# OurEDA-P1K_PowerManagement.net
KiCad netlist of a schematic drawn in Altium Designer
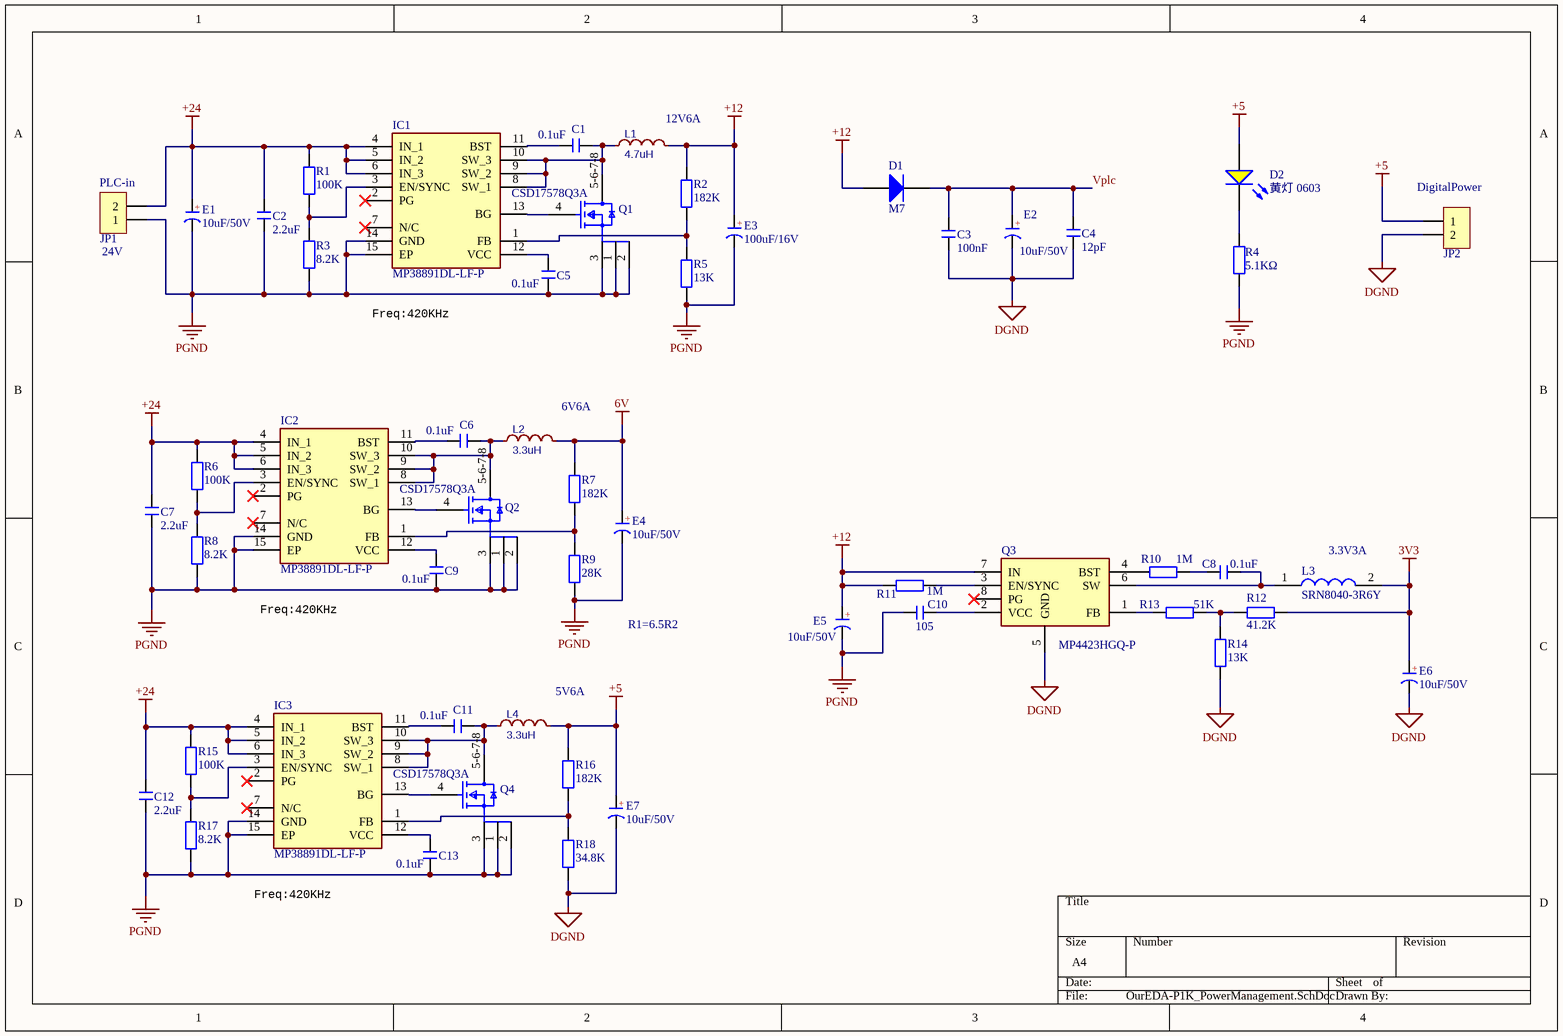
[diagram p0: OurEDA-P1K_PowerManagement.SchDoc]

(export (version "E")
  (design (tool "Eeschema 10.0.6"))
  (components
    (comp (ref "C1")
      (value "0.1uF")
      (footprint "C 0603_L")
      (description "无极性贴片电容")
      (fields (field (name "版权归属") "源创客"))
      (libsource (lib "3.1   - 电阻-电容-电感") (part "C"))
    )
    (comp (ref "C2")
      (value "2.2uF")
      (footprint "C 0805_L")
      (description "无极性贴片电容")
      (fields (field (name "版权归属") "源创客"))
      (libsource (lib "3.1   - 电阻-电容-电感") (part "C"))
    )
    (comp (ref "C3")
      (value "100nF")
      (footprint "C 0603_L")
      (description "无极性贴片电容")
      (fields (field (name "版权归属") "源创客"))
      (libsource (lib "3.1   - 电阻-电容-电感") (part "C"))
    )
    (comp (ref "C4")
      (value "12pF")
      (footprint "C 0603_L")
      (description "无极性贴片电容")
      (fields (field (name "版权归属") "源创客"))
      (libsource (lib "3.1   - 电阻-电容-电感") (part "C"))
    )
    (comp (ref "C5")
      (value "0.1uF")
      (footprint "C 0603_L")
      (description "无极性贴片电容")
      (fields (field (name "版权归属") "源创客"))
      (libsource (lib "3.1   - 电阻-电容-电感") (part "C"))
    )
    (comp (ref "C6")
      (value "0.1uF")
      (footprint "C 0603_L")
      (description "无极性贴片电容")
      (fields (field (name "版权归属") "源创客"))
      (libsource (lib "3.1   - 电阻-电容-电感") (part "C"))
    )
    (comp (ref "C7")
      (value "2.2uF")
      (footprint "C 0805_L")
      (description "无极性贴片电容")
      (fields (field (name "版权归属") "源创客"))
      (libsource (lib "3.1   - 电阻-电容-电感") (part "C"))
    )
    (comp (ref "C8")
      (value "0.1uF")
      (footprint "C 0603_L")
      (description "无极性贴片电容")
      (fields (field (name "版权归属") "源创客"))
      (libsource (lib "3.1   - 电阻-电容-电感") (part "C"))
    )
    (comp (ref "C9")
      (value "0.1uF")
      (footprint "C 0603_L")
      (description "无极性贴片电容")
      (fields (field (name "版权归属") "源创客"))
      (libsource (lib "3.1   - 电阻-电容-电感") (part "C"))
    )
    (comp (ref "C10")
      (value "105")
      (footprint "C 0603_L")
      (description "无极性贴片电容")
      (fields (field (name "版权归属") "源创客"))
      (libsource (lib "3.1   - 电阻-电容-电感") (part "C"))
    )
    (comp (ref "C11")
      (value "0.1uF")
      (footprint "C 0603_L")
      (description "无极性贴片电容")
      (fields (field (name "版权归属") "源创客"))
      (libsource (lib "3.1   - 电阻-电容-电感") (part "C"))
    )
    (comp (ref "C12")
      (value "2.2uF")
      (footprint "C 0805_L")
      (description "无极性贴片电容")
      (fields (field (name "版权归属") "源创客"))
      (libsource (lib "3.1   - 电阻-电容-电感") (part "C"))
    )
    (comp (ref "C13")
      (value "0.1uF")
      (footprint "C 0603_L")
      (description "无极性贴片电容")
      (fields (field (name "版权归属") "源创客"))
      (libsource (lib "3.1   - 电阻-电容-电感") (part "C"))
    )
    (comp (ref "D1")
      (value "M7")
      (footprint "SMA(DO-214AC)_S1")
      (description "二极管")
      (libsource (lib "Miscellaneous Devices LC") (part "SMA(DO-214AC) M7"))
    )
    (comp (ref "D2")
      (value "黄灯 0603")
      (footprint "0603_LED_S1")
      (description "发光二极管")
      (libsource (lib "Miscellaneous Devices LC") (part "0603 黄灯"))
    )
    (comp (ref "E1")
      (value "10uF/50V")
      (footprint "CM D(6.3*5.4)")
      (description "贴片电解电容")
      (fields (field (name "版权归属") "源创客"))
      (libsource (lib "3.1   - 电阻-电容-电感") (part "C-CM"))
    )
    (comp (ref "E2")
      (value "10uF/50V")
      (footprint "CM B(4*5.4)")
      (description "贴片电解电容")
      (fields (field (name "版权归属") "源创客"))
      (libsource (lib "3.1   - 电阻-电容-电感") (part "C-CM"))
    )
    (comp (ref "E3")
      (value "100uF/16V")
      (footprint "CM D(6.3*5.4)")
      (description "贴片电解电容")
      (fields (field (name "版权归属") "源创客"))
      (libsource (lib "3.1   - 电阻-电容-电感") (part "C-CM"))
    )
    (comp (ref "E4")
      (value "10uF/50V")
      (footprint "CM B(4*5.4)")
      (description "贴片电解电容")
      (fields (field (name "版权归属") "源创客"))
      (libsource (lib "3.1   - 电阻-电容-电感") (part "C-CM"))
    )
    (comp (ref "E5")
      (value "10uF/50V")
      (footprint "CM B(4*5.4)")
      (description "贴片电解电容")
      (fields (field (name "版权归属") "源创客"))
      (libsource (lib "3.1   - 电阻-电容-电感") (part "C-CM"))
    )
    (comp (ref "E6")
      (value "10uF/50V")
      (footprint "CM B(4*5.4)")
      (description "贴片电解电容")
      (fields (field (name "版权归属") "源创客"))
      (libsource (lib "3.1   - 电阻-电容-电感") (part "C-CM"))
    )
    (comp (ref "E7")
      (value "10uF/50V")
      (footprint "CM B(4*5.4)")
      (description "贴片电解电容")
      (fields (field (name "版权归属") "源创客"))
      (libsource (lib "3.1   - 电阻-电容-电感") (part "C-CM"))
    )
    (comp (ref "IC1")
      (value "MP38891DL-LF-P")
      (footprint "SON50P300X400X100-15N-D")
      (description "Integrated Circuit")
      (fields (field (name "MOUSER PART NUMBER") "946-MP38891DLLFP"))
      (libsource (lib "MySchLib") (part "MP38891DL-LF-P"))
    )
    (comp (ref "IC2")
      (value "MP38891DL-LF-P")
      (footprint "SON50P300X400X100-15N-D")
      (description "Integrated Circuit")
      (fields (field (name "MOUSER PART NUMBER") "946-MP38891DLLFP"))
      (libsource (lib "MySchLib") (part "MP38891DL-LF-P"))
    )
    (comp (ref "IC3")
      (value "MP38891DL-LF-P")
      (footprint "SON50P300X400X100-15N-D")
      (description "Integrated Circuit")
      (fields (field (name "MOUSER PART NUMBER") "946-MP38891DLLFP"))
      (libsource (lib "MySchLib") (part "MP38891DL-LF-P"))
    )
    (comp (ref "JP1")
      (value "HDR-1X2")
      (footprint "KF128-5.08-2P")
      (description "2P接插件")
      (fields (field (name "版权归属") "源创客"))
      (libsource (lib "4.10 - 接插件-脚距5.08") (part "Header 2"))
    )
    (comp (ref "JP2")
      (value "HDR-1X2")
      (footprint "HDR2.54-LI-2P")
      (description "2P接插件")
      (fields (field (name "版权归属") "源创客"))
      (libsource (lib "4.5   - 接插件-脚距2.54") (part "Header 2"))
    )
    (comp (ref "L1")
      (value "4.7uH")
      (footprint "220uH")
      (fields
        (field (name "BOM_SUPPLIER PART") "C364099")
        (field (name "BOM_MANUFACTURER PART") "SLO1235H220MTT")
        (field (name "CONTRIBUTOR") "LCSC")
      )
      (libsource (lib "MySchLib") (part "220uH"))
    )
    (comp (ref "L2")
      (value "3.3uH")
      (footprint "220uH")
      (fields
        (field (name "BOM_SUPPLIER PART") "C364099")
        (field (name "BOM_MANUFACTURER PART") "SLO1235H220MTT")
        (field (name "CONTRIBUTOR") "LCSC")
      )
      (libsource (lib "MySchLib") (part "220uH"))
    )
    (comp (ref "L3")
      (value "SRN8040-3R6Y")
      (footprint "SRN80408R2Y")
      (description "Inductor")
      (fields (field (name "MOUSER PART NUMBER") "652-SRN8040-3R6Y"))
      (libsource (lib "*") (part "SRN8040-3R6Y"))
    )
    (comp (ref "L4")
      (value "3.3uH")
      (footprint "220uH")
      (fields
        (field (name "BOM_SUPPLIER PART") "C364099")
        (field (name "BOM_MANUFACTURER PART") "SLO1235H220MTT")
        (field (name "CONTRIBUTOR") "LCSC")
      )
      (libsource (lib "MySchLib") (part "220uH"))
    )
    (comp (ref "Q1")
      (value "CSD17578Q3A")
      (footprint "FP-DNH0008A-MFG")
      (description "MOSFET N-CH 30V 35A 8VSON")
      (libsource (lib "Altium Content Vault") (part "89a476aaa9378d44880e05315291ed4"))
    )
    (comp (ref "Q2")
      (value "CSD17578Q3A")
      (footprint "FP-DNH0008A-MFG")
      (description "MOSFET N-CH 30V 35A 8VSON")
      (libsource (lib "Altium Content Vault") (part "89a476aaa9378d44880e05315291ed4"))
    )
    (comp (ref "Q3")
      (value "MP4423HGQ-P")
      (footprint "MP4423GQP")
      (description "Transistor")
      (fields (field (name "MOUSER PART NUMBER") "946-MP4423HGQ-P"))
      (libsource (lib "MySchLib") (part "MP4423HGQ-P"))
    )
    (comp (ref "Q4")
      (value "CSD17578Q3A")
      (footprint "FP-DNH0008A-MFG")
      (description "MOSFET N-CH 30V 35A 8VSON")
      (libsource (lib "Altium Content Vault") (part "89a476aaa9378d44880e05315291ed4"))
    )
    (comp (ref "R1")
      (value "100K")
      (footprint "R 0603_L")
      (description "贴片电阻")
      (fields (field (name "版权归属") "源创客"))
      (libsource (lib "3.1   - 电阻-电容-电感") (part "R"))
    )
    (comp (ref "R2")
      (value "182K")
      (footprint "R 0603_L")
      (description "贴片电阻")
      (fields (field (name "版权归属") "源创客"))
      (libsource (lib "3.1   - 电阻-电容-电感") (part "R"))
    )
    (comp (ref "R3")
      (value "8.2K")
      (footprint "R 0603_L")
      (description "贴片电阻")
      (fields (field (name "版权归属") "源创客"))
      (libsource (lib "3.1   - 电阻-电容-电感") (part "R"))
    )
    (comp (ref "R4")
      (value "5.1KΩ")
      (footprint "0603_R")
      (description "贴片电阻")
      (libsource (lib "Miscellaneous Devices LC") (part "0603 3.3KΩ (3301) 1%"))
    )
    (comp (ref "R5")
      (value "13K")
      (footprint "R 0603_L")
      (description "贴片电阻")
      (fields (field (name "版权归属") "源创客"))
      (libsource (lib "3.1   - 电阻-电容-电感") (part "R"))
    )
    (comp (ref "R6")
      (value "100K")
      (footprint "R 0603_L")
      (description "贴片电阻")
      (fields (field (name "版权归属") "源创客"))
      (libsource (lib "3.1   - 电阻-电容-电感") (part "R"))
    )
    (comp (ref "R7")
      (value "182K")
      (footprint "R 0603_L")
      (description "贴片电阻")
      (fields (field (name "版权归属") "源创客"))
      (libsource (lib "3.1   - 电阻-电容-电感") (part "R"))
    )
    (comp (ref "R8")
      (value "8.2K")
      (footprint "R 0603_L")
      (description "贴片电阻")
      (fields (field (name "版权归属") "源创客"))
      (libsource (lib "3.1   - 电阻-电容-电感") (part "R"))
    )
    (comp (ref "R9")
      (value "28K")
      (footprint "R 0603_L")
      (description "贴片电阻")
      (fields (field (name "版权归属") "源创客"))
      (libsource (lib "3.1   - 电阻-电容-电感") (part "R"))
    )
    (comp (ref "R10")
      (value "1M")
      (footprint "R 0603_L")
      (description "贴片电阻")
      (fields (field (name "版权归属") "源创客"))
      (libsource (lib "3.1   - 电阻-电容-电感") (part "R"))
    )
    (comp (ref "R11")
      (value "1M")
      (footprint "R 0603_L")
      (description "贴片电阻")
      (fields (field (name "版权归属") "源创客"))
      (libsource (lib "3.1   - 电阻-电容-电感") (part "R"))
    )
    (comp (ref "R12")
      (value "41.2K")
      (footprint "R 0603_L")
      (description "贴片电阻")
      (fields (field (name "版权归属") "源创客"))
      (libsource (lib "3.1   - 电阻-电容-电感") (part "R"))
    )
    (comp (ref "R13")
      (value "51K")
      (footprint "R 0603_L")
      (description "贴片电阻")
      (fields (field (name "版权归属") "源创客"))
      (libsource (lib "3.1   - 电阻-电容-电感") (part "R"))
    )
    (comp (ref "R14")
      (value "13K")
      (footprint "R 0603_L")
      (description "贴片电阻")
      (fields (field (name "版权归属") "源创客"))
      (libsource (lib "3.1   - 电阻-电容-电感") (part "R"))
    )
    (comp (ref "R15")
      (value "100K")
      (footprint "R 0603_L")
      (description "贴片电阻")
      (fields (field (name "版权归属") "源创客"))
      (libsource (lib "3.1   - 电阻-电容-电感") (part "R"))
    )
    (comp (ref "R16")
      (value "182K")
      (footprint "R 0603_L")
      (description "贴片电阻")
      (fields (field (name "版权归属") "源创客"))
      (libsource (lib "3.1   - 电阻-电容-电感") (part "R"))
    )
    (comp (ref "R17")
      (value "8.2K")
      (footprint "R 0603_L")
      (description "贴片电阻")
      (fields (field (name "版权归属") "源创客"))
      (libsource (lib "3.1   - 电阻-电容-电感") (part "R"))
    )
    (comp (ref "R18")
      (value "34.8K")
      (footprint "R 0603_L")
      (description "贴片电阻")
      (fields (field (name "版权归属") "源创客"))
      (libsource (lib "3.1   - 电阻-电容-电感") (part "R"))
    )
  )
  (nets
    (net (code "1") (name "+5") (class "Default")
      (node (ref "D2") (pin "A") (pinfunction "A_A") (pintype "passive"))
      (node (ref "E7") (pin "1") (pinfunction "A_1") (pintype "passive"))
      (node (ref "JP2") (pin "1") (pinfunction "1_1") (pintype "passive"))
      (node (ref "L4") (pin "2") (pinfunction "2_2") (pintype "passive"))
      (node (ref "R16") (pin "2") (pinfunction "2_2") (pintype "passive"))
    )
    (net (code "2") (name "+12") (class "Default")
      (node (ref "D1") (pin "1") (pinfunction "A_1") (pintype "passive"))
      (node (ref "E3") (pin "1") (pinfunction "A_1") (pintype "passive"))
      (node (ref "E5") (pin "1") (pinfunction "A_1") (pintype "passive"))
      (node (ref "L1") (pin "2") (pinfunction "2_2") (pintype "passive"))
      (node (ref "Q3") (pin "7") (pinfunction "IN_7") (pintype "passive"))
      (node (ref "R11") (pin "2") (pinfunction "2_2") (pintype "passive"))
      (node (ref "R2") (pin "2") (pinfunction "2_2") (pintype "passive"))
    )
    (net (code "3") (name "+24") (class "Default")
      (node (ref "C12") (pin "2") (pinfunction "2_2") (pintype "passive"))
      (node (ref "C2") (pin "2") (pinfunction "2_2") (pintype "passive"))
      (node (ref "C7") (pin "2") (pinfunction "2_2") (pintype "passive"))
      (node (ref "E1") (pin "1") (pinfunction "A_1") (pintype "passive"))
      (node (ref "IC1") (pin "4") (pinfunction "IN_1_4") (pintype "passive"))
      (node (ref "IC1") (pin "5") (pinfunction "IN_2_5") (pintype "passive"))
      (node (ref "IC1") (pin "6") (pinfunction "IN_3_6") (pintype "passive"))
      (node (ref "IC2") (pin "4") (pinfunction "IN_1_4") (pintype "passive"))
      (node (ref "IC2") (pin "5") (pinfunction "IN_2_5") (pintype "passive"))
      (node (ref "IC2") (pin "6") (pinfunction "IN_3_6") (pintype "passive"))
      (node (ref "IC3") (pin "4") (pinfunction "IN_1_4") (pintype "passive"))
      (node (ref "IC3") (pin "5") (pinfunction "IN_2_5") (pintype "passive"))
      (node (ref "IC3") (pin "6") (pinfunction "IN_3_6") (pintype "passive"))
      (node (ref "JP1") (pin "2") (pinfunction "2_2") (pintype "passive"))
      (node (ref "R1") (pin "2") (pinfunction "2_2") (pintype "passive"))
      (node (ref "R15") (pin "2") (pinfunction "2_2") (pintype "passive"))
      (node (ref "R6") (pin "2") (pinfunction "2_2") (pintype "passive"))
    )
    (net (code "4") (name "/Vplc") (class "Default")
      (node (ref "C3") (pin "1") (pinfunction "1_1") (pintype "passive"))
      (node (ref "C4") (pin "1") (pinfunction "1_1") (pintype "passive"))
      (node (ref "D1") (pin "2") (pinfunction "K_2") (pintype "passive"))
      (node (ref "E2") (pin "1") (pinfunction "A_1") (pintype "passive"))
    )
    (net (code "5") (name "3V3") (class "Default")
      (node (ref "E6") (pin "1") (pinfunction "A_1") (pintype "passive"))
      (node (ref "L3") (pin "2") (pinfunction "2_2") (pintype "passive"))
      (node (ref "R12") (pin "2") (pinfunction "2_2") (pintype "passive"))
    )
    (net (code "6") (name "6V") (class "Default")
      (node (ref "E4") (pin "1") (pinfunction "A_1") (pintype "passive"))
      (node (ref "L2") (pin "2") (pinfunction "2_2") (pintype "passive"))
      (node (ref "R7") (pin "2") (pinfunction "2_2") (pintype "passive"))
    )
    (net (code "7") (name "DGND") (class "Default")
      (node (ref "C3") (pin "2") (pinfunction "2_2") (pintype "passive"))
      (node (ref "C4") (pin "2") (pinfunction "2_2") (pintype "passive"))
      (node (ref "E2") (pin "2") (pinfunction "K_2") (pintype "passive"))
      (node (ref "E6") (pin "2") (pinfunction "K_2") (pintype "passive"))
      (node (ref "E7") (pin "2") (pinfunction "K_2") (pintype "passive"))
      (node (ref "JP2") (pin "2") (pinfunction "2_2") (pintype "passive"))
      (node (ref "Q3") (pin "5") (pinfunction "GND_5") (pintype "passive"))
      (node (ref "R14") (pin "2") (pinfunction "2_2") (pintype "passive"))
      (node (ref "R18") (pin "1") (pinfunction "1_1") (pintype "passive"))
    )
    (net (code "8") (name "Net-(C8-Pad2)") (class "Default")
      (node (ref "C8") (pin "2") (pinfunction "2_2") (pintype "passive"))
      (node (ref "R10") (pin "1") (pinfunction "1_1") (pintype "passive"))
    )
    (net (code "9") (name "Net-(D2-PadK)") (class "Default")
      (node (ref "D2") (pin "K") (pinfunction "K_K") (pintype "passive"))
      (node (ref "R4") (pin "1") (pinfunction "1_1") (pintype "passive"))
    )
    (net (code "10") (name "Net-(IC1-BG)") (class "Default")
      (node (ref "IC1") (pin "13") (pinfunction "BG_13") (pintype "passive"))
      (node (ref "Q1") (pin "4") (pinfunction "G_4") (pintype "passive"))
    )
    (net (code "11") (name "Net-(IC1-BST)") (class "Default")
      (node (ref "C1") (pin "2") (pinfunction "2_2") (pintype "passive"))
      (node (ref "IC1") (pin "11") (pinfunction "BST_11") (pintype "passive"))
    )
    (net (code "12") (name "Net-(IC1-EN{slash}SYNC)") (class "Default")
      (node (ref "IC1") (pin "3") (pinfunction "EN/SYNC_3") (pintype "passive"))
      (node (ref "R1") (pin "1") (pinfunction "1_1") (pintype "passive"))
      (node (ref "R3") (pin "2") (pinfunction "2_2") (pintype "passive"))
    )
    (net (code "13") (name "Net-(IC1-FB)") (class "Default")
      (node (ref "IC1") (pin "1") (pinfunction "FB_1") (pintype "passive"))
      (node (ref "R2") (pin "1") (pinfunction "1_1") (pintype "passive"))
      (node (ref "R5") (pin "2") (pinfunction "2_2") (pintype "passive"))
    )
    (net (code "14") (name "Net-(IC1-SW_1)") (class "Default")
      (node (ref "C1") (pin "1") (pinfunction "1_1") (pintype "passive"))
      (node (ref "IC1") (pin "10") (pinfunction "SW_3_10") (pintype "passive"))
      (node (ref "IC1") (pin "8") (pinfunction "SW_1_8") (pintype "passive"))
      (node (ref "IC1") (pin "9") (pinfunction "SW_2_9") (pintype "passive"))
      (node (ref "L1") (pin "1") (pinfunction "1_1") (pintype "passive"))
      (node (ref "Q1") (pin "5-6-7-8") (pinfunction "D_5-6-7-8") (pintype "passive"))
    )
    (net (code "15") (name "Net-(IC1-VCC)") (class "Default")
      (node (ref "C5") (pin "1") (pinfunction "1_1") (pintype "passive"))
      (node (ref "IC1") (pin "12") (pinfunction "VCC_12") (pintype "passive"))
    )
    (net (code "16") (name "Net-(IC2-BG)") (class "Default")
      (node (ref "IC2") (pin "13") (pinfunction "BG_13") (pintype "passive"))
      (node (ref "Q2") (pin "4") (pinfunction "G_4") (pintype "passive"))
    )
    (net (code "17") (name "Net-(IC2-BST)") (class "Default")
      (node (ref "C6") (pin "2") (pinfunction "2_2") (pintype "passive"))
      (node (ref "IC2") (pin "11") (pinfunction "BST_11") (pintype "passive"))
    )
    (net (code "18") (name "Net-(IC2-EN{slash}SYNC)") (class "Default")
      (node (ref "IC2") (pin "3") (pinfunction "EN/SYNC_3") (pintype "passive"))
      (node (ref "R6") (pin "1") (pinfunction "1_1") (pintype "passive"))
      (node (ref "R8") (pin "2") (pinfunction "2_2") (pintype "passive"))
    )
    (net (code "19") (name "Net-(IC2-FB)") (class "Default")
      (node (ref "IC2") (pin "1") (pinfunction "FB_1") (pintype "passive"))
      (node (ref "R7") (pin "1") (pinfunction "1_1") (pintype "passive"))
      (node (ref "R9") (pin "2") (pinfunction "2_2") (pintype "passive"))
    )
    (net (code "20") (name "Net-(IC2-SW_1)") (class "Default")
      (node (ref "C6") (pin "1") (pinfunction "1_1") (pintype "passive"))
      (node (ref "IC2") (pin "10") (pinfunction "SW_3_10") (pintype "passive"))
      (node (ref "IC2") (pin "8") (pinfunction "SW_1_8") (pintype "passive"))
      (node (ref "IC2") (pin "9") (pinfunction "SW_2_9") (pintype "passive"))
      (node (ref "L2") (pin "1") (pinfunction "1_1") (pintype "passive"))
      (node (ref "Q2") (pin "5-6-7-8") (pinfunction "D_5-6-7-8") (pintype "passive"))
    )
    (net (code "21") (name "Net-(IC2-VCC)") (class "Default")
      (node (ref "C9") (pin "1") (pinfunction "1_1") (pintype "passive"))
      (node (ref "IC2") (pin "12") (pinfunction "VCC_12") (pintype "passive"))
    )
    (net (code "22") (name "Net-(IC3-BG)") (class "Default")
      (node (ref "IC3") (pin "13") (pinfunction "BG_13") (pintype "passive"))
      (node (ref "Q4") (pin "4") (pinfunction "G_4") (pintype "passive"))
    )
    (net (code "23") (name "Net-(IC3-BST)") (class "Default")
      (node (ref "C11") (pin "2") (pinfunction "2_2") (pintype "passive"))
      (node (ref "IC3") (pin "11") (pinfunction "BST_11") (pintype "passive"))
    )
    (net (code "24") (name "Net-(IC3-EN{slash}SYNC)") (class "Default")
      (node (ref "IC3") (pin "3") (pinfunction "EN/SYNC_3") (pintype "passive"))
      (node (ref "R15") (pin "1") (pinfunction "1_1") (pintype "passive"))
      (node (ref "R17") (pin "2") (pinfunction "2_2") (pintype "passive"))
    )
    (net (code "25") (name "Net-(IC3-FB)") (class "Default")
      (node (ref "IC3") (pin "1") (pinfunction "FB_1") (pintype "passive"))
      (node (ref "R16") (pin "1") (pinfunction "1_1") (pintype "passive"))
      (node (ref "R18") (pin "2") (pinfunction "2_2") (pintype "passive"))
    )
    (net (code "26") (name "Net-(IC3-SW_1)") (class "Default")
      (node (ref "C11") (pin "1") (pinfunction "1_1") (pintype "passive"))
      (node (ref "IC3") (pin "10") (pinfunction "SW_3_10") (pintype "passive"))
      (node (ref "IC3") (pin "8") (pinfunction "SW_1_8") (pintype "passive"))
      (node (ref "IC3") (pin "9") (pinfunction "SW_2_9") (pintype "passive"))
      (node (ref "L4") (pin "1") (pinfunction "1_1") (pintype "passive"))
      (node (ref "Q4") (pin "5-6-7-8") (pinfunction "D_5-6-7-8") (pintype "passive"))
    )
    (net (code "27") (name "Net-(IC3-VCC)") (class "Default")
      (node (ref "C13") (pin "1") (pinfunction "1_1") (pintype "passive"))
      (node (ref "IC3") (pin "12") (pinfunction "VCC_12") (pintype "passive"))
    )
    (net (code "28") (name "Net-(Q3-BST)") (class "Default")
      (node (ref "Q3") (pin "4") (pinfunction "BST_4") (pintype "passive"))
      (node (ref "R10") (pin "2") (pinfunction "2_2") (pintype "passive"))
    )
    (net (code "29") (name "Net-(Q3-EN{slash}SYNC)") (class "Default")
      (node (ref "Q3") (pin "3") (pinfunction "EN/SYNC_3") (pintype "passive"))
      (node (ref "R11") (pin "1") (pinfunction "1_1") (pintype "passive"))
    )
    (net (code "30") (name "Net-(Q3-FB)") (class "Default")
      (node (ref "Q3") (pin "1") (pinfunction "FB_1") (pintype "passive"))
      (node (ref "R13") (pin "2") (pinfunction "2_2") (pintype "passive"))
    )
    (net (code "31") (name "Net-(Q3-SW)") (class "Default")
      (node (ref "C8") (pin "1") (pinfunction "1_1") (pintype "passive"))
      (node (ref "L3") (pin "1") (pinfunction "1_1") (pintype "passive"))
      (node (ref "Q3") (pin "6") (pinfunction "SW_6") (pintype "passive"))
    )
    (net (code "32") (name "Net-(Q3-VCC)") (class "Default")
      (node (ref "C10") (pin "2") (pinfunction "2_2") (pintype "passive"))
      (node (ref "Q3") (pin "2") (pinfunction "VCC_2") (pintype "passive"))
    )
    (net (code "33") (name "Net-(R12-Pad1)") (class "Default")
      (node (ref "R12") (pin "1") (pinfunction "1_1") (pintype "passive"))
      (node (ref "R13") (pin "1") (pinfunction "1_1") (pintype "passive"))
      (node (ref "R14") (pin "1") (pinfunction "1_1") (pintype "passive"))
    )
    (net (code "34") (name "PGND") (class "Default")
      (node (ref "C10") (pin "1") (pinfunction "1_1") (pintype "passive"))
      (node (ref "C12") (pin "1") (pinfunction "1_1") (pintype "passive"))
      (node (ref "C13") (pin "2") (pinfunction "2_2") (pintype "passive"))
      (node (ref "C2") (pin "1") (pinfunction "1_1") (pintype "passive"))
      (node (ref "C5") (pin "2") (pinfunction "2_2") (pintype "passive"))
      (node (ref "C7") (pin "1") (pinfunction "1_1") (pintype "passive"))
      (node (ref "C9") (pin "2") (pinfunction "2_2") (pintype "passive"))
      (node (ref "E1") (pin "2") (pinfunction "K_2") (pintype "passive"))
      (node (ref "E3") (pin "2") (pinfunction "K_2") (pintype "passive"))
      (node (ref "E4") (pin "2") (pinfunction "K_2") (pintype "passive"))
      (node (ref "E5") (pin "2") (pinfunction "K_2") (pintype "passive"))
      (node (ref "IC1") (pin "14") (pinfunction "GND_14") (pintype "passive"))
      (node (ref "IC1") (pin "15") (pinfunction "EP_15") (pintype "passive"))
      (node (ref "IC2") (pin "14") (pinfunction "GND_14") (pintype "passive"))
      (node (ref "IC2") (pin "15") (pinfunction "EP_15") (pintype "passive"))
      (node (ref "IC3") (pin "14") (pinfunction "GND_14") (pintype "passive"))
      (node (ref "IC3") (pin "15") (pinfunction "EP_15") (pintype "passive"))
      (node (ref "JP1") (pin "1") (pinfunction "1_1") (pintype "passive"))
      (node (ref "Q1") (pin "1") (pinfunction "S_1") (pintype "passive"))
      (node (ref "Q1") (pin "2") (pinfunction "S_2") (pintype "passive"))
      (node (ref "Q1") (pin "3") (pinfunction "S_3") (pintype "passive"))
      (node (ref "Q2") (pin "1") (pinfunction "S_1") (pintype "passive"))
      (node (ref "Q2") (pin "2") (pinfunction "S_2") (pintype "passive"))
      (node (ref "Q2") (pin "3") (pinfunction "S_3") (pintype "passive"))
      (node (ref "Q4") (pin "1") (pinfunction "S_1") (pintype "passive"))
      (node (ref "Q4") (pin "2") (pinfunction "S_2") (pintype "passive"))
      (node (ref "Q4") (pin "3") (pinfunction "S_3") (pintype "passive"))
      (node (ref "R17") (pin "1") (pinfunction "1_1") (pintype "passive"))
      (node (ref "R3") (pin "1") (pinfunction "1_1") (pintype "passive"))
      (node (ref "R4") (pin "2") (pinfunction "2_2") (pintype "passive"))
      (node (ref "R5") (pin "1") (pinfunction "1_1") (pintype "passive"))
      (node (ref "R8") (pin "1") (pinfunction "1_1") (pintype "passive"))
      (node (ref "R9") (pin "1") (pinfunction "1_1") (pintype "passive"))
    )
    (net (code "35") (name "unconnected-(IC1-N{slash}C-Pad7)") (class "Default")
      (node (ref "IC1") (pin "7") (pinfunction "N/C_7") (pintype "passive+no_connect"))
    )
    (net (code "36") (name "unconnected-(IC1-PG-Pad2)") (class "Default")
      (node (ref "IC1") (pin "2") (pinfunction "PG_2") (pintype "passive+no_connect"))
    )
    (net (code "37") (name "unconnected-(IC2-N{slash}C-Pad7)") (class "Default")
      (node (ref "IC2") (pin "7") (pinfunction "N/C_7") (pintype "passive+no_connect"))
    )
    (net (code "38") (name "unconnected-(IC2-PG-Pad2)") (class "Default")
      (node (ref "IC2") (pin "2") (pinfunction "PG_2") (pintype "passive+no_connect"))
    )
    (net (code "39") (name "unconnected-(IC3-N{slash}C-Pad7)") (class "Default")
      (node (ref "IC3") (pin "7") (pinfunction "N/C_7") (pintype "passive+no_connect"))
    )
    (net (code "40") (name "unconnected-(IC3-PG-Pad2)") (class "Default")
      (node (ref "IC3") (pin "2") (pinfunction "PG_2") (pintype "passive+no_connect"))
    )
    (net (code "41") (name "unconnected-(Q3-PG-Pad8)") (class "Default")
      (node (ref "Q3") (pin "8") (pinfunction "PG_8") (pintype "passive+no_connect"))
    )
  )
)
